# control.net
KiCad netlist of a schematic drawn in EAGLE
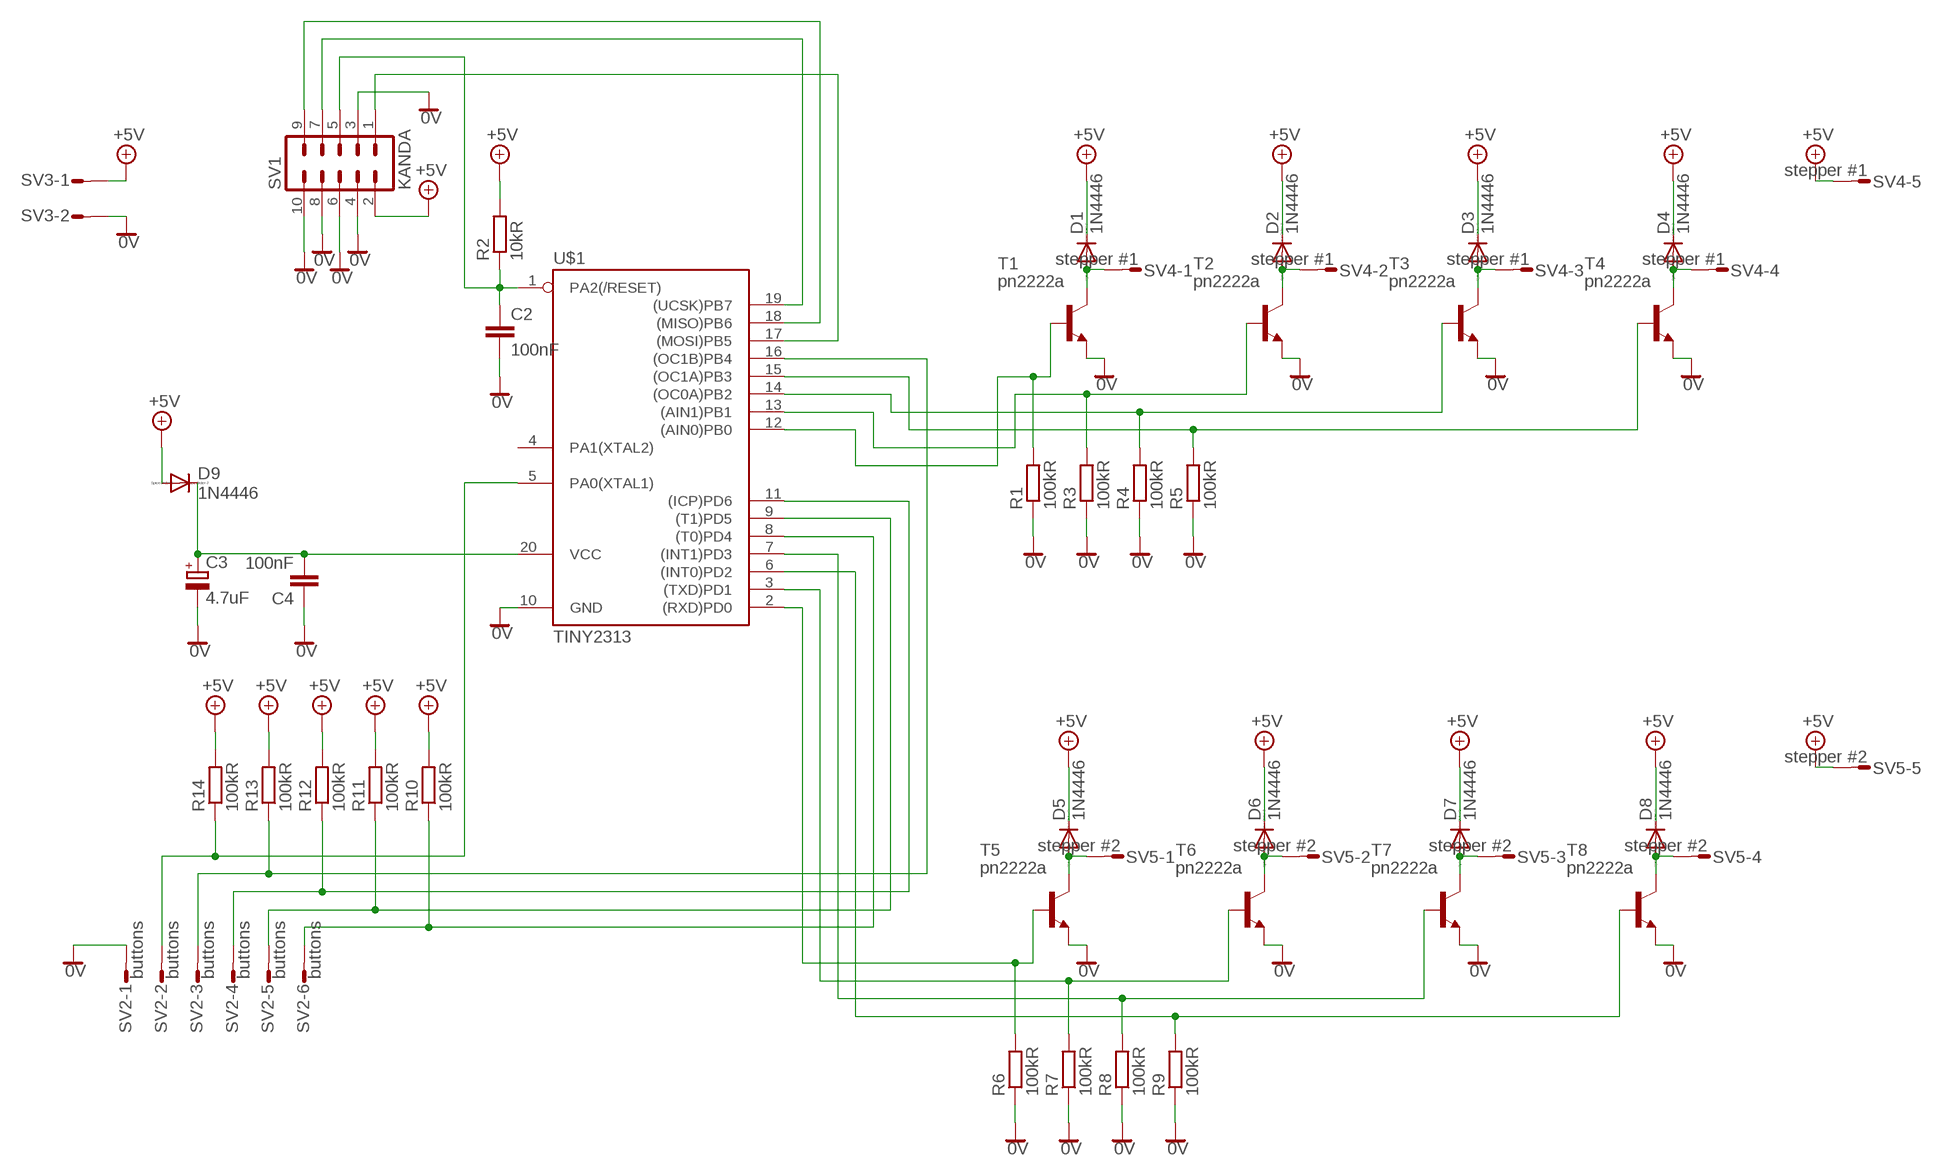
[diagram p0: schematic, sheet 1]

(export (version "E")
  (design (tool "Eeschema 10.0.6"))
  (components
    (comp (ref "C2")
      (value "100nF")
      (footprint "eagle-import:C3216")
      (libsource (lib "eagle-import") (part "C-EUC3216"))
    )
    (comp (ref "C3")
      (value "4.7uF")
      (footprint "eagle-import:153CLV-0405")
      (libsource (lib "eagle-import") (part "CPOL-EU153CLV-0405"))
    )
    (comp (ref "C4")
      (value "100nF")
      (footprint "eagle-import:C3216")
      (libsource (lib "eagle-import") (part "C-EUC3216"))
    )
    (comp (ref "D1")
      (value "1N4446")
      (footprint "eagle-import:DO35-10")
      (libsource (lib "eagle-import") (part "1N4446"))
    )
    (comp (ref "D2")
      (value "1N4446")
      (footprint "eagle-import:DO35-10")
      (libsource (lib "eagle-import") (part "1N4446"))
    )
    (comp (ref "D3")
      (value "1N4446")
      (footprint "eagle-import:DO35-10")
      (libsource (lib "eagle-import") (part "1N4446"))
    )
    (comp (ref "D4")
      (value "1N4446")
      (footprint "eagle-import:DO35-10")
      (libsource (lib "eagle-import") (part "1N4446"))
    )
    (comp (ref "D5")
      (value "1N4446")
      (footprint "eagle-import:DO35-10")
      (libsource (lib "eagle-import") (part "1N4446"))
    )
    (comp (ref "D6")
      (value "1N4446")
      (footprint "eagle-import:DO35-10")
      (libsource (lib "eagle-import") (part "1N4446"))
    )
    (comp (ref "D7")
      (value "1N4446")
      (footprint "eagle-import:DO35-10")
      (libsource (lib "eagle-import") (part "1N4446"))
    )
    (comp (ref "D8")
      (value "1N4446")
      (footprint "eagle-import:DO35-10")
      (libsource (lib "eagle-import") (part "1N4446"))
    )
    (comp (ref "D9")
      (value "1N4446")
      (footprint "eagle-import:DO35-10")
      (libsource (lib "eagle-import") (part "1N4446"))
    )
    (comp (ref "R1")
      (value "100kR")
      (footprint "eagle-import:MINI_MELF-0204W")
      (libsource (lib "eagle-import") (part "R-EU_MELF0204W"))
    )
    (comp (ref "R2")
      (value "10kR")
      (footprint "eagle-import:MINI_MELF-0204W")
      (libsource (lib "eagle-import") (part "R-EU_MELF0204W"))
    )
    (comp (ref "R3")
      (value "100kR")
      (footprint "eagle-import:MINI_MELF-0204W")
      (libsource (lib "eagle-import") (part "R-EU_MELF0204W"))
    )
    (comp (ref "R4")
      (value "100kR")
      (footprint "eagle-import:MINI_MELF-0204W")
      (libsource (lib "eagle-import") (part "R-EU_MELF0204W"))
    )
    (comp (ref "R5")
      (value "100kR")
      (footprint "eagle-import:MINI_MELF-0204W")
      (libsource (lib "eagle-import") (part "R-EU_MELF0204W"))
    )
    (comp (ref "R6")
      (value "100kR")
      (footprint "eagle-import:MINI_MELF-0204W")
      (libsource (lib "eagle-import") (part "R-EU_MELF0204W"))
    )
    (comp (ref "R7")
      (value "100kR")
      (footprint "eagle-import:MINI_MELF-0204W")
      (libsource (lib "eagle-import") (part "R-EU_MELF0204W"))
    )
    (comp (ref "R8")
      (value "100kR")
      (footprint "eagle-import:MINI_MELF-0204W")
      (libsource (lib "eagle-import") (part "R-EU_MELF0204W"))
    )
    (comp (ref "R9")
      (value "100kR")
      (footprint "eagle-import:MINI_MELF-0204W")
      (libsource (lib "eagle-import") (part "R-EU_MELF0204W"))
    )
    (comp (ref "R10")
      (value "100kR")
      (footprint "eagle-import:MINI_MELF-0204W")
      (libsource (lib "eagle-import") (part "R-EU_MELF0204W"))
    )
    (comp (ref "R11")
      (value "100kR")
      (footprint "eagle-import:MINI_MELF-0204W")
      (libsource (lib "eagle-import") (part "R-EU_MELF0204W"))
    )
    (comp (ref "R12")
      (value "100kR")
      (footprint "eagle-import:MINI_MELF-0204W")
      (libsource (lib "eagle-import") (part "R-EU_MELF0204W"))
    )
    (comp (ref "R13")
      (value "100kR")
      (footprint "eagle-import:MINI_MELF-0204W")
      (libsource (lib "eagle-import") (part "R-EU_MELF0204W"))
    )
    (comp (ref "R14")
      (value "100kR")
      (footprint "eagle-import:MINI_MELF-0204W")
      (libsource (lib "eagle-import") (part "R-EU_MELF0204W"))
    )
    (comp (ref "SV1")
      (value "KANDA")
      (footprint "eagle-import:ML10")
      (libsource (lib "eagle-import") (part "ML10"))
    )
    (comp (ref "SV2")
      (value "buttons")
      (footprint "eagle-import:S06P")
      (libsource (lib "eagle-import") (part "S06P"))
    )
    (comp (ref "SV3")
      (value "S02P")
      (footprint "eagle-import:S02P")
      (libsource (lib "eagle-import") (part "S02P"))
    )
    (comp (ref "SV4")
      (value "stepper #1")
      (footprint "eagle-import:S05P")
      (libsource (lib "eagle-import") (part "S05P"))
    )
    (comp (ref "SV5")
      (value "stepper #2")
      (footprint "eagle-import:S05P")
      (libsource (lib "eagle-import") (part "S05P"))
    )
    (comp (ref "T1")
      (value "pn2222a")
      (footprint "eagle-import:TO92-CBE")
      (libsource (lib "eagle-import") (part "-NPN-TO92-CBEMPS2222A"))
    )
    (comp (ref "T2")
      (value "pn2222a")
      (footprint "eagle-import:TO92-CBE")
      (libsource (lib "eagle-import") (part "-NPN-TO92-CBEMPS2222A"))
    )
    (comp (ref "T3")
      (value "pn2222a")
      (footprint "eagle-import:TO92-CBE")
      (libsource (lib "eagle-import") (part "-NPN-TO92-CBEMPS2222A"))
    )
    (comp (ref "T4")
      (value "pn2222a")
      (footprint "eagle-import:TO92-CBE")
      (libsource (lib "eagle-import") (part "-NPN-TO92-CBEMPS2222A"))
    )
    (comp (ref "T5")
      (value "pn2222a")
      (footprint "eagle-import:TO92-CBE")
      (libsource (lib "eagle-import") (part "-NPN-TO92-CBEMPS2222A"))
    )
    (comp (ref "T6")
      (value "pn2222a")
      (footprint "eagle-import:TO92-CBE")
      (libsource (lib "eagle-import") (part "-NPN-TO92-CBEMPS2222A"))
    )
    (comp (ref "T7")
      (value "pn2222a")
      (footprint "eagle-import:TO92-CBE")
      (libsource (lib "eagle-import") (part "-NPN-TO92-CBEMPS2222A"))
    )
    (comp (ref "T8")
      (value "pn2222a")
      (footprint "eagle-import:TO92-CBE")
      (libsource (lib "eagle-import") (part "-NPN-TO92-CBEMPS2222A"))
    )
    (comp (ref "U$1")
      (value "TINY2313")
      (footprint "eagle-import:DIL20")
      (libsource (lib "eagle-import") (part "TINY2313-P"))
    )
  )
  (nets
    (net (code "1") (name "+5V") (class "Default")
      (node (ref "D1") (pin "C") (pinfunction "C_C") (pintype "passive"))
      (node (ref "D2") (pin "C") (pinfunction "C_C") (pintype "passive"))
      (node (ref "D3") (pin "C") (pinfunction "C_C") (pintype "passive"))
      (node (ref "D4") (pin "C") (pinfunction "C_C") (pintype "passive"))
      (node (ref "D5") (pin "C") (pinfunction "C_C") (pintype "passive"))
      (node (ref "D6") (pin "C") (pinfunction "C_C") (pintype "passive"))
      (node (ref "D7") (pin "C") (pinfunction "C_C") (pintype "passive"))
      (node (ref "D8") (pin "C") (pinfunction "C_C") (pintype "passive"))
      (node (ref "D9") (pin "A") (pinfunction "A_A") (pintype "passive"))
      (node (ref "R10") (pin "2") (pinfunction "2_2") (pintype "passive"))
      (node (ref "R11") (pin "2") (pinfunction "2_2") (pintype "passive"))
      (node (ref "R12") (pin "2") (pinfunction "2_2") (pintype "passive"))
      (node (ref "R13") (pin "2") (pinfunction "2_2") (pintype "passive"))
      (node (ref "R14") (pin "2") (pinfunction "2_2") (pintype "passive"))
      (node (ref "R2") (pin "2") (pinfunction "2_2") (pintype "passive"))
      (node (ref "SV1") (pin "2") (pinfunction "2_2") (pintype "passive"))
      (node (ref "SV3") (pin "1") (pinfunction "S_1") (pintype "passive"))
      (node (ref "SV4") (pin "5") (pinfunction "S_5") (pintype "passive"))
      (node (ref "SV5") (pin "5") (pinfunction "S_5") (pintype "passive"))
    )
    (net (code "2") (name "0V") (class "Default")
      (node (ref "C2") (pin "2") (pinfunction "2_2") (pintype "passive"))
      (node (ref "C3") (pin "-") (pinfunction "-_-") (pintype "passive"))
      (node (ref "C4") (pin "1") (pinfunction "1_1") (pintype "passive"))
      (node (ref "R1") (pin "1") (pinfunction "1_1") (pintype "passive"))
      (node (ref "R3") (pin "1") (pinfunction "1_1") (pintype "passive"))
      (node (ref "R4") (pin "1") (pinfunction "1_1") (pintype "passive"))
      (node (ref "R5") (pin "1") (pinfunction "1_1") (pintype "passive"))
      (node (ref "R6") (pin "1") (pinfunction "1_1") (pintype "passive"))
      (node (ref "R7") (pin "1") (pinfunction "1_1") (pintype "passive"))
      (node (ref "R8") (pin "1") (pinfunction "1_1") (pintype "passive"))
      (node (ref "R9") (pin "1") (pinfunction "1_1") (pintype "passive"))
      (node (ref "SV1") (pin "10") (pinfunction "10_10") (pintype "passive"))
      (node (ref "SV1") (pin "3") (pinfunction "3_3") (pintype "passive"))
      (node (ref "SV1") (pin "4") (pinfunction "4_4") (pintype "passive"))
      (node (ref "SV1") (pin "6") (pinfunction "6_6") (pintype "passive"))
      (node (ref "SV1") (pin "8") (pinfunction "8_8") (pintype "passive"))
      (node (ref "SV2") (pin "1") (pinfunction "S_1") (pintype "passive"))
      (node (ref "SV3") (pin "2") (pinfunction "S_2") (pintype "passive"))
      (node (ref "T1") (pin "E") (pinfunction "E_E") (pintype "passive"))
      (node (ref "T2") (pin "E") (pinfunction "E_E") (pintype "passive"))
      (node (ref "T3") (pin "E") (pinfunction "E_E") (pintype "passive"))
      (node (ref "T4") (pin "E") (pinfunction "E_E") (pintype "passive"))
      (node (ref "T5") (pin "E") (pinfunction "E_E") (pintype "passive"))
      (node (ref "T6") (pin "E") (pinfunction "E_E") (pintype "passive"))
      (node (ref "T7") (pin "E") (pinfunction "E_E") (pintype "passive"))
      (node (ref "T8") (pin "E") (pinfunction "E_E") (pintype "passive"))
      (node (ref "U$1") (pin "10") (pinfunction "GND_10") (pintype "power_in"))
    )
    (net (code "3") (name "Net-(SV2B-S)") (class "Default")
      (node (ref "R14") (pin "1") (pinfunction "1_1") (pintype "passive"))
      (node (ref "SV2") (pin "2") (pinfunction "S_2") (pintype "passive"))
      (node (ref "U$1") (pin "5") (pinfunction "PA0(XTAL1)_5") (pintype "bidirectional"))
    )
    (net (code "4") (name "Net-(SV2C-S)") (class "Default")
      (node (ref "R13") (pin "1") (pinfunction "1_1") (pintype "passive"))
      (node (ref "SV2") (pin "3") (pinfunction "S_3") (pintype "passive"))
      (node (ref "U$1") (pin "16") (pinfunction "(OC1B)PB4_16") (pintype "bidirectional"))
    )
    (net (code "5") (name "Net-(SV2D-S)") (class "Default")
      (node (ref "R12") (pin "1") (pinfunction "1_1") (pintype "passive"))
      (node (ref "SV2") (pin "4") (pinfunction "S_4") (pintype "passive"))
      (node (ref "U$1") (pin "11") (pinfunction "(ICP)PD6_11") (pintype "bidirectional"))
    )
    (net (code "6") (name "Net-(SV2E-S)") (class "Default")
      (node (ref "R11") (pin "1") (pinfunction "1_1") (pintype "passive"))
      (node (ref "SV2") (pin "5") (pinfunction "S_5") (pintype "passive"))
      (node (ref "U$1") (pin "9") (pinfunction "(T1)PD5_9") (pintype "bidirectional"))
    )
    (net (code "7") (name "Net-(SV2F-S)") (class "Default")
      (node (ref "R10") (pin "1") (pinfunction "1_1") (pintype "passive"))
      (node (ref "SV2") (pin "6") (pinfunction "S_6") (pintype "passive"))
      (node (ref "U$1") (pin "8") (pinfunction "(T0)PD4_8") (pintype "bidirectional"))
    )
    (net (code "8") (name "Net-(SV4A-S)") (class "Default")
      (node (ref "D1") (pin "A") (pinfunction "A_A") (pintype "passive"))
      (node (ref "SV4") (pin "1") (pinfunction "S_1") (pintype "passive"))
      (node (ref "T1") (pin "C") (pinfunction "C_C") (pintype "passive"))
    )
    (net (code "9") (name "Net-(SV4B-S)") (class "Default")
      (node (ref "D2") (pin "A") (pinfunction "A_A") (pintype "passive"))
      (node (ref "SV4") (pin "2") (pinfunction "S_2") (pintype "passive"))
      (node (ref "T2") (pin "C") (pinfunction "C_C") (pintype "passive"))
    )
    (net (code "10") (name "Net-(SV4C-S)") (class "Default")
      (node (ref "D3") (pin "A") (pinfunction "A_A") (pintype "passive"))
      (node (ref "SV4") (pin "3") (pinfunction "S_3") (pintype "passive"))
      (node (ref "T3") (pin "C") (pinfunction "C_C") (pintype "passive"))
    )
    (net (code "11") (name "Net-(SV4D-S)") (class "Default")
      (node (ref "D4") (pin "A") (pinfunction "A_A") (pintype "passive"))
      (node (ref "SV4") (pin "4") (pinfunction "S_4") (pintype "passive"))
      (node (ref "T4") (pin "C") (pinfunction "C_C") (pintype "passive"))
    )
    (net (code "12") (name "Net-(SV5A-S)") (class "Default")
      (node (ref "D5") (pin "A") (pinfunction "A_A") (pintype "passive"))
      (node (ref "SV5") (pin "1") (pinfunction "S_1") (pintype "passive"))
      (node (ref "T5") (pin "C") (pinfunction "C_C") (pintype "passive"))
    )
    (net (code "13") (name "Net-(SV5B-S)") (class "Default")
      (node (ref "D6") (pin "A") (pinfunction "A_A") (pintype "passive"))
      (node (ref "SV5") (pin "2") (pinfunction "S_2") (pintype "passive"))
      (node (ref "T6") (pin "C") (pinfunction "C_C") (pintype "passive"))
    )
    (net (code "14") (name "Net-(SV5C-S)") (class "Default")
      (node (ref "D7") (pin "A") (pinfunction "A_A") (pintype "passive"))
      (node (ref "SV5") (pin "3") (pinfunction "S_3") (pintype "passive"))
      (node (ref "T7") (pin "C") (pinfunction "C_C") (pintype "passive"))
    )
    (net (code "15") (name "Net-(SV5D-S)") (class "Default")
      (node (ref "D8") (pin "A") (pinfunction "A_A") (pintype "passive"))
      (node (ref "SV5") (pin "4") (pinfunction "S_4") (pintype "passive"))
      (node (ref "T8") (pin "C") (pinfunction "C_C") (pintype "passive"))
    )
    (net (code "16") (name "Net-(U$1-(AIN0)PB0)") (class "Default")
      (node (ref "R1") (pin "2") (pinfunction "2_2") (pintype "passive"))
      (node (ref "T1") (pin "B") (pinfunction "B_B") (pintype "passive"))
      (node (ref "U$1") (pin "12") (pinfunction "(AIN0)PB0_12") (pintype "bidirectional"))
    )
    (net (code "17") (name "Net-(U$1-(AIN1)PB1)") (class "Default")
      (node (ref "R3") (pin "2") (pinfunction "2_2") (pintype "passive"))
      (node (ref "T2") (pin "B") (pinfunction "B_B") (pintype "passive"))
      (node (ref "U$1") (pin "13") (pinfunction "(AIN1)PB1_13") (pintype "bidirectional"))
    )
    (net (code "18") (name "Net-(U$1-(INT0)PD2)") (class "Default")
      (node (ref "R9") (pin "2") (pinfunction "2_2") (pintype "passive"))
      (node (ref "T8") (pin "B") (pinfunction "B_B") (pintype "passive"))
      (node (ref "U$1") (pin "6") (pinfunction "(INT0)PD2_6") (pintype "bidirectional"))
    )
    (net (code "19") (name "Net-(U$1-(INT1)PD3)") (class "Default")
      (node (ref "R8") (pin "2") (pinfunction "2_2") (pintype "passive"))
      (node (ref "T7") (pin "B") (pinfunction "B_B") (pintype "passive"))
      (node (ref "U$1") (pin "7") (pinfunction "(INT1)PD3_7") (pintype "bidirectional"))
    )
    (net (code "20") (name "Net-(U$1-(MISO)PB6)") (class "Default")
      (node (ref "SV1") (pin "9") (pinfunction "9_9") (pintype "passive"))
      (node (ref "U$1") (pin "18") (pinfunction "(MISO)PB6_18") (pintype "bidirectional"))
    )
    (net (code "21") (name "Net-(U$1-(MOSI)PB5)") (class "Default")
      (node (ref "SV1") (pin "1") (pinfunction "1_1") (pintype "passive"))
      (node (ref "U$1") (pin "17") (pinfunction "(MOSI)PB5_17") (pintype "bidirectional"))
    )
    (net (code "22") (name "Net-(U$1-(OC0A)PB2)") (class "Default")
      (node (ref "R4") (pin "2") (pinfunction "2_2") (pintype "passive"))
      (node (ref "T3") (pin "B") (pinfunction "B_B") (pintype "passive"))
      (node (ref "U$1") (pin "14") (pinfunction "(OC0A)PB2_14") (pintype "bidirectional"))
    )
    (net (code "23") (name "Net-(U$1-(OC1A)PB3)") (class "Default")
      (node (ref "R5") (pin "2") (pinfunction "2_2") (pintype "passive"))
      (node (ref "T4") (pin "B") (pinfunction "B_B") (pintype "passive"))
      (node (ref "U$1") (pin "15") (pinfunction "(OC1A)PB3_15") (pintype "bidirectional"))
    )
    (net (code "24") (name "Net-(U$1-(RXD)PD0)") (class "Default")
      (node (ref "R6") (pin "2") (pinfunction "2_2") (pintype "passive"))
      (node (ref "T5") (pin "B") (pinfunction "B_B") (pintype "passive"))
      (node (ref "U$1") (pin "2") (pinfunction "(RXD)PD0_2") (pintype "bidirectional"))
    )
    (net (code "25") (name "Net-(U$1-(TXD)PD1)") (class "Default")
      (node (ref "R7") (pin "2") (pinfunction "2_2") (pintype "passive"))
      (node (ref "T6") (pin "B") (pinfunction "B_B") (pintype "passive"))
      (node (ref "U$1") (pin "3") (pinfunction "(TXD)PD1_3") (pintype "bidirectional"))
    )
    (net (code "26") (name "Net-(U$1-(UCSK)PB7)") (class "Default")
      (node (ref "SV1") (pin "7") (pinfunction "7_7") (pintype "passive"))
      (node (ref "U$1") (pin "19") (pinfunction "(UCSK)PB7_19") (pintype "bidirectional"))
    )
    (net (code "27") (name "Net-(U$1-PA2({slash}RESET))") (class "Default")
      (node (ref "C2") (pin "1") (pinfunction "1_1") (pintype "passive"))
      (node (ref "R2") (pin "1") (pinfunction "1_1") (pintype "passive"))
      (node (ref "SV1") (pin "5") (pinfunction "5_5") (pintype "passive"))
      (node (ref "U$1") (pin "1") (pinfunction "PA2(/RESET)_1") (pintype "input"))
    )
    (net (code "28") (name "Net-(U$1-VCC)") (class "Default")
      (node (ref "C3") (pin "+") (pinfunction "+_+") (pintype "passive"))
      (node (ref "C4") (pin "2") (pinfunction "2_2") (pintype "passive"))
      (node (ref "D9") (pin "C") (pinfunction "C_C") (pintype "passive"))
      (node (ref "U$1") (pin "20") (pinfunction "VCC_20") (pintype "power_in"))
    )
    (net (code "29") (name "unconnected-(U$1-PA1(XTAL2)-Pad4)") (class "Default")
      (node (ref "U$1") (pin "4") (pinfunction "PA1(XTAL2)_4") (pintype "bidirectional"))
    )
  )
)
